# OpenMV-Main.net
KiCad netlist of a schematic drawn in Altium Designer
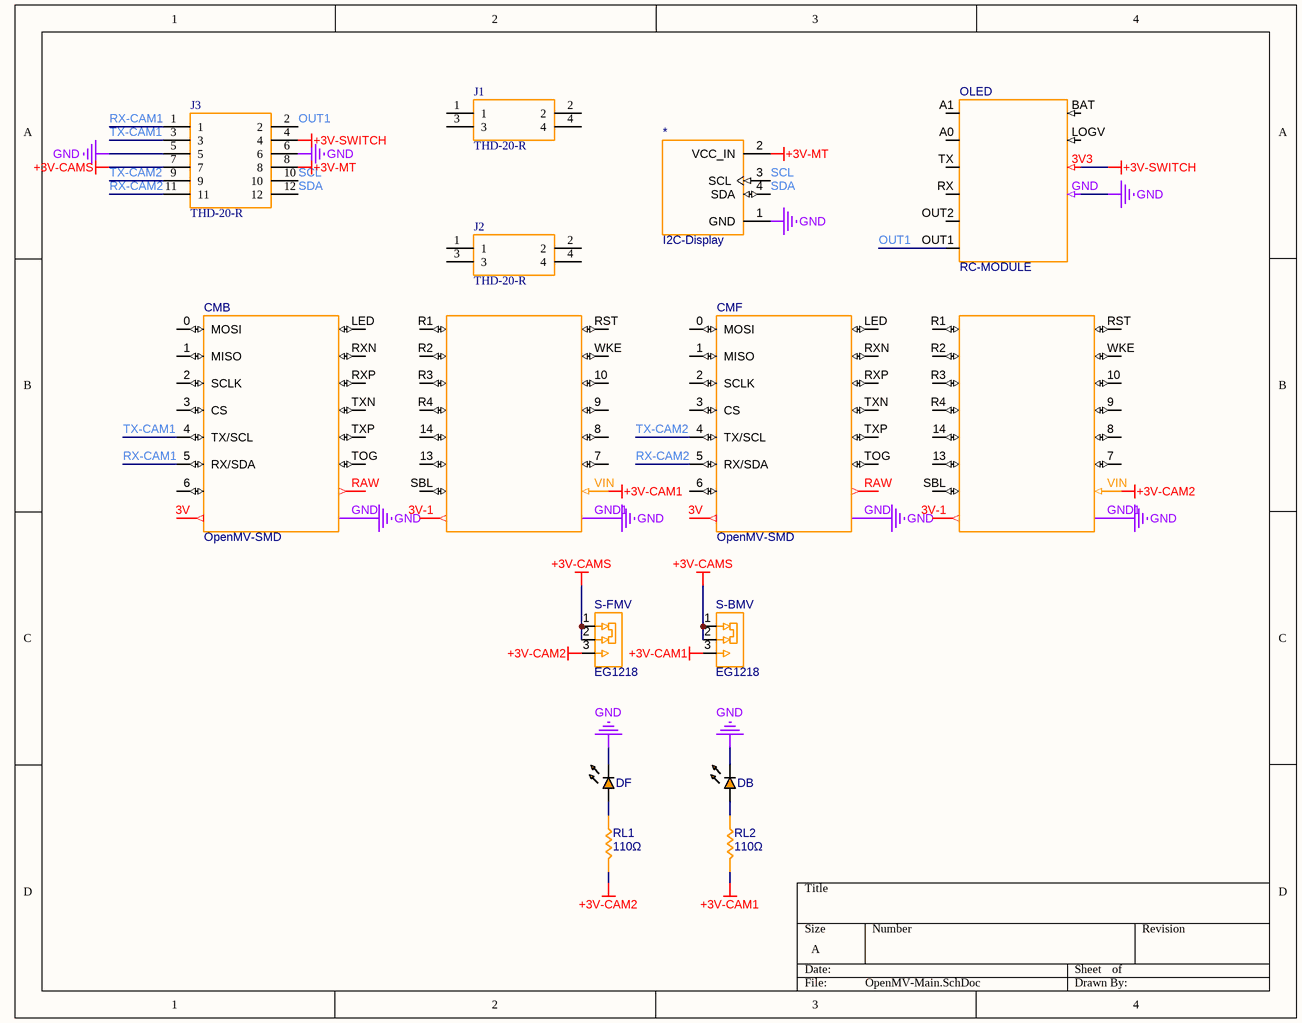
[diagram p0: OpenMV-Main.SchDoc]

(export (version "E")
  (design (tool "Eeschema 10.0.6"))
  (components
    (comp (ref "*")
      (value "I2C-Display")
      (footprint "I2C-Display")
      (libsource (lib "RC") (part "I2C-Display"))
    )
    (comp (ref "CMB")
      (value "OpenMV-SMD")
      (footprint "OpenMV-SMD")
      (libsource (lib "RC") (part "OpenMV-SMD"))
    )
    (comp (ref "CMF")
      (value "OpenMV-SMD")
      (footprint "OpenMV-SMD")
      (libsource (lib "RC") (part "OpenMV-SMD"))
    )
    (comp (ref "DB")
      (value "LED_0603")
      (footprint "LED_0603")
      (libsource (lib "GenericRC") (part "LED_0603"))
    )
    (comp (ref "DF")
      (value "LED_0603")
      (footprint "LED_0603")
      (libsource (lib "GenericRC") (part "LED_0603"))
    )
    (comp (ref "J1")
      (value "THD-20-R")
      (footprint "VALCON_THD-20-R")
      (description "THD - Valcon 2.54mm Pitch Dual Row Pin Header - Fast Stock")
      (fields (field (name "MF") "Valcon"))
      (libsource (lib "THD-20-R") (part "THD-20-R"))
    )
    (comp (ref "J2")
      (value "THD-20-R")
      (footprint "VALCON_THD-20-R")
      (description "THD - Valcon 2.54mm Pitch Dual Row Pin Header - Fast Stock")
      (fields (field (name "MF") "Valcon"))
      (libsource (lib "THD-20-R") (part "THD-20-R"))
    )
    (comp (ref "J3")
      (value "THD-20-R")
      (footprint "VALCON_THD-20-R")
      (description "THD - Valcon 2.54mm Pitch Dual Row Pin Header - Fast Stock")
      (fields (field (name "MF") "Valcon"))
      (libsource (lib "THD-12-R") (part "THD-20-R"))
    )
    (comp (ref "OLED") (value "RC-MODULE") (footprint "RC-MODULE") (libsource (lib "RC") (part "RC-MODULE")))
    (comp (ref "RL1")
      (value "110Ω")
      (footprint "RES_0603")
      (description "Resistor SMD 0603 generic")
      (libsource (lib "GenericRC") (part "RES_0603"))
    )
    (comp (ref "RL2")
      (value "110Ω")
      (footprint "RES_0603")
      (description "Resistor SMD 0603 generic")
      (libsource (lib "GenericRC") (part "RES_0603"))
    )
    (comp (ref "S-BMV")
      (value "EG1218")
      (footprint "EG1218")
      (libsource (lib "ChaBots Phoenix") (part "EG1218"))
    )
    (comp (ref "S-FMV")
      (value "EG1218")
      (footprint "EG1218")
      (libsource (lib "ChaBots Phoenix") (part "EG1218"))
    )
  )
  (nets
    (net (code "1") (name "+3V-CAM1") (class "Default")
      (node (ref "CMB") (pin "VIN") (pintype "input"))
      (node (ref "RL2") (pin "1") (pintype "passive"))
      (node (ref "S-BMV") (pin "3") (pinfunction "NO_3") (pintype "passive"))
    )
    (net (code "2") (name "+3V-CAM2") (class "Default")
      (node (ref "CMF") (pin "VIN") (pintype "input"))
      (node (ref "RL1") (pin "1") (pintype "passive"))
      (node (ref "S-FMV") (pin "3") (pinfunction "NO_3") (pintype "passive"))
    )
    (net (code "3") (name "+3V-CAMS") (class "Default")
      (node (ref "J3") (pin "7") (pinfunction "7_7") (pintype "passive"))
      (node (ref "S-BMV") (pin "1") (pinfunction "NC_1") (pintype "passive"))
      (node (ref "S-BMV") (pin "2") (pinfunction "COM_2") (pintype "passive"))
      (node (ref "S-FMV") (pin "1") (pinfunction "NC_1") (pintype "passive"))
      (node (ref "S-FMV") (pin "2") (pinfunction "COM_2") (pintype "passive"))
    )
    (net (code "4") (name "+3V-MT") (class "Default")
      (node (ref "*") (pin "2") (pinfunction "VCC_IN_2") (pintype "power_in"))
      (node (ref "J3") (pin "8") (pinfunction "8_8") (pintype "passive"))
    )
    (net (code "5") (name "+3V-SWITCH") (class "Default")
      (node (ref "J3") (pin "4") (pinfunction "4_4") (pintype "passive"))
      (node (ref "OLED") (pin "3V3") (pintype "input"))
    )
    (net (code "6") (name "/OUT1") (class "Default")
      (node (ref "J3") (pin "2") (pinfunction "2_2") (pintype "passive"))
      (node (ref "OLED") (pin "OUT1") (pintype "bidirectional"))
    )
    (net (code "7") (name "/RX-CAM1") (class "Default")
      (node (ref "CMB") (pin "5") (pinfunction "RX/SDA_5") (pintype "bidirectional"))
      (node (ref "J3") (pin "1") (pinfunction "1_1") (pintype "passive"))
    )
    (net (code "8") (name "/RX-CAM2") (class "Default")
      (node (ref "CMF") (pin "5") (pinfunction "RX/SDA_5") (pintype "bidirectional"))
      (node (ref "J3") (pin "11") (pinfunction "11_11") (pintype "passive"))
    )
    (net (code "9") (name "/SCL") (class "Default")
      (node (ref "*") (pin "3") (pinfunction "SCL_3") (pintype "input"))
      (node (ref "J3") (pin "10") (pinfunction "10_10") (pintype "passive"))
    )
    (net (code "10") (name "/SDA") (class "Default")
      (node (ref "*") (pin "4") (pinfunction "SDA_4") (pintype "bidirectional"))
      (node (ref "J3") (pin "12") (pinfunction "12_12") (pintype "passive"))
    )
    (net (code "11") (name "/TX-CAM1") (class "Default")
      (node (ref "CMB") (pin "4") (pinfunction "TX/SCL_4") (pintype "bidirectional"))
      (node (ref "J3") (pin "3") (pinfunction "3_3") (pintype "passive"))
    )
    (net (code "12") (name "/TX-CAM2") (class "Default")
      (node (ref "CMF") (pin "4") (pinfunction "TX/SCL_4") (pintype "bidirectional"))
      (node (ref "J3") (pin "9") (pinfunction "9_9") (pintype "passive"))
    )
    (net (code "13") (name "GND") (class "Default")
      (node (ref "*") (pin "1") (pinfunction "GND_1") (pintype "power_in"))
      (node (ref "CMB") (pin "GND") (pintype "passive"))
      (node (ref "CMB") (pin "GND1") (pintype "passive"))
      (node (ref "CMF") (pin "GND") (pintype "passive"))
      (node (ref "CMF") (pin "GND1") (pintype "passive"))
      (node (ref "DB") (pin "C") (pinfunction "1_C") (pintype "passive"))
      (node (ref "DF") (pin "C") (pinfunction "1_C") (pintype "passive"))
      (node (ref "J3") (pin "5") (pinfunction "5_5") (pintype "passive"))
      (node (ref "J3") (pin "6") (pinfunction "6_6") (pintype "passive"))
      (node (ref "OLED") (pin "GND") (pintype "input"))
    )
    (net (code "14") (name "Net-(DB-2)") (class "Default")
      (node (ref "DB") (pin "A") (pinfunction "2_A") (pintype "passive"))
      (node (ref "RL2") (pin "2") (pintype "passive"))
    )
    (net (code "15") (name "Net-(DF-2)") (class "Default")
      (node (ref "DF") (pin "A") (pinfunction "2_A") (pintype "passive"))
      (node (ref "RL1") (pin "2") (pintype "passive"))
    )
    (net (code "16") (name "unconnected-(CMB-CS-Pad3)") (class "Default")
      (node (ref "CMB") (pin "3") (pinfunction "CS_3") (pintype "bidirectional"))
    )
    (net (code "17") (name "unconnected-(CMB-MISO-Pad1)") (class "Default")
      (node (ref "CMB") (pin "1") (pinfunction "MISO_1") (pintype "bidirectional"))
    )
    (net (code "18") (name "unconnected-(CMB-MOSI-Pad0)") (class "Default")
      (node (ref "CMB") (pin "0") (pinfunction "MOSI_0") (pintype "bidirectional"))
    )
    (net (code "19") (name "unconnected-(CMB-Pad3V)") (class "Default")
      (node (ref "CMB") (pin "3V") (pintype "output"))
    )
    (net (code "20") (name "unconnected-(CMB-Pad3V-1)") (class "Default")
      (node (ref "CMB") (pin "3V-1") (pintype "output"))
    )
    (net (code "21") (name "unconnected-(CMB-Pad6)") (class "Default")
      (node (ref "CMB") (pin "6") (pintype "bidirectional"))
    )
    (net (code "22") (name "unconnected-(CMB-Pad7)") (class "Default")
      (node (ref "CMB") (pin "7") (pintype "bidirectional"))
    )
    (net (code "23") (name "unconnected-(CMB-Pad8)") (class "Default")
      (node (ref "CMB") (pin "8") (pintype "bidirectional"))
    )
    (net (code "24") (name "unconnected-(CMB-Pad9)") (class "Default")
      (node (ref "CMB") (pin "9") (pintype "bidirectional"))
    )
    (net (code "25") (name "unconnected-(CMB-Pad10)") (class "Default")
      (node (ref "CMB") (pin "10") (pintype "bidirectional"))
    )
    (net (code "26") (name "unconnected-(CMB-Pad13)") (class "Default")
      (node (ref "CMB") (pin "13") (pintype "bidirectional"))
    )
    (net (code "27") (name "unconnected-(CMB-Pad14)") (class "Default")
      (node (ref "CMB") (pin "14") (pintype "bidirectional"))
    )
    (net (code "28") (name "unconnected-(CMB-PadLED)") (class "Default")
      (node (ref "CMB") (pin "LED") (pintype "bidirectional"))
    )
    (net (code "29") (name "unconnected-(CMB-PadR1)") (class "Default")
      (node (ref "CMB") (pin "R1") (pintype "bidirectional"))
    )
    (net (code "30") (name "unconnected-(CMB-PadR2)") (class "Default")
      (node (ref "CMB") (pin "R2") (pintype "bidirectional"))
    )
    (net (code "31") (name "unconnected-(CMB-PadR3)") (class "Default")
      (node (ref "CMB") (pin "R3") (pintype "bidirectional"))
    )
    (net (code "32") (name "unconnected-(CMB-PadR4)") (class "Default")
      (node (ref "CMB") (pin "R4") (pintype "bidirectional"))
    )
    (net (code "33") (name "unconnected-(CMB-PadRAW)") (class "Default")
      (node (ref "CMB") (pin "RAW") (pintype "output"))
    )
    (net (code "34") (name "unconnected-(CMB-PadRST)") (class "Default")
      (node (ref "CMB") (pin "RST") (pintype "bidirectional"))
    )
    (net (code "35") (name "unconnected-(CMB-PadRXN)") (class "Default")
      (node (ref "CMB") (pin "RXN") (pintype "bidirectional"))
    )
    (net (code "36") (name "unconnected-(CMB-PadRXP)") (class "Default")
      (node (ref "CMB") (pin "RXP") (pintype "bidirectional"))
    )
    (net (code "37") (name "unconnected-(CMB-PadSBL)") (class "Default")
      (node (ref "CMB") (pin "SBL") (pintype "bidirectional"))
    )
    (net (code "38") (name "unconnected-(CMB-PadTOG)") (class "Default")
      (node (ref "CMB") (pin "TOG") (pintype "bidirectional"))
    )
    (net (code "39") (name "unconnected-(CMB-PadTXN)") (class "Default")
      (node (ref "CMB") (pin "TXN") (pintype "bidirectional"))
    )
    (net (code "40") (name "unconnected-(CMB-PadTXP)") (class "Default")
      (node (ref "CMB") (pin "TXP") (pintype "bidirectional"))
    )
    (net (code "41") (name "unconnected-(CMB-PadWKE)") (class "Default")
      (node (ref "CMB") (pin "WKE") (pintype "bidirectional"))
    )
    (net (code "42") (name "unconnected-(CMB-SCLK-Pad2)") (class "Default")
      (node (ref "CMB") (pin "2") (pinfunction "SCLK_2") (pintype "bidirectional"))
    )
    (net (code "43") (name "unconnected-(CMF-CS-Pad3)") (class "Default")
      (node (ref "CMF") (pin "3") (pinfunction "CS_3") (pintype "bidirectional"))
    )
    (net (code "44") (name "unconnected-(CMF-MISO-Pad1)") (class "Default")
      (node (ref "CMF") (pin "1") (pinfunction "MISO_1") (pintype "bidirectional"))
    )
    (net (code "45") (name "unconnected-(CMF-MOSI-Pad0)") (class "Default")
      (node (ref "CMF") (pin "0") (pinfunction "MOSI_0") (pintype "bidirectional"))
    )
    (net (code "46") (name "unconnected-(CMF-Pad3V)") (class "Default")
      (node (ref "CMF") (pin "3V") (pintype "output"))
    )
    (net (code "47") (name "unconnected-(CMF-Pad3V-1)") (class "Default")
      (node (ref "CMF") (pin "3V-1") (pintype "output"))
    )
    (net (code "48") (name "unconnected-(CMF-Pad6)") (class "Default")
      (node (ref "CMF") (pin "6") (pintype "bidirectional"))
    )
    (net (code "49") (name "unconnected-(CMF-Pad7)") (class "Default")
      (node (ref "CMF") (pin "7") (pintype "bidirectional"))
    )
    (net (code "50") (name "unconnected-(CMF-Pad8)") (class "Default")
      (node (ref "CMF") (pin "8") (pintype "bidirectional"))
    )
    (net (code "51") (name "unconnected-(CMF-Pad9)") (class "Default")
      (node (ref "CMF") (pin "9") (pintype "bidirectional"))
    )
    (net (code "52") (name "unconnected-(CMF-Pad10)") (class "Default")
      (node (ref "CMF") (pin "10") (pintype "bidirectional"))
    )
    (net (code "53") (name "unconnected-(CMF-Pad13)") (class "Default")
      (node (ref "CMF") (pin "13") (pintype "bidirectional"))
    )
    (net (code "54") (name "unconnected-(CMF-Pad14)") (class "Default")
      (node (ref "CMF") (pin "14") (pintype "bidirectional"))
    )
    (net (code "55") (name "unconnected-(CMF-PadLED)") (class "Default")
      (node (ref "CMF") (pin "LED") (pintype "bidirectional"))
    )
    (net (code "56") (name "unconnected-(CMF-PadR1)") (class "Default")
      (node (ref "CMF") (pin "R1") (pintype "bidirectional"))
    )
    (net (code "57") (name "unconnected-(CMF-PadR2)") (class "Default")
      (node (ref "CMF") (pin "R2") (pintype "bidirectional"))
    )
    (net (code "58") (name "unconnected-(CMF-PadR3)") (class "Default")
      (node (ref "CMF") (pin "R3") (pintype "bidirectional"))
    )
    (net (code "59") (name "unconnected-(CMF-PadR4)") (class "Default")
      (node (ref "CMF") (pin "R4") (pintype "bidirectional"))
    )
    (net (code "60") (name "unconnected-(CMF-PadRAW)") (class "Default")
      (node (ref "CMF") (pin "RAW") (pintype "output"))
    )
    (net (code "61") (name "unconnected-(CMF-PadRST)") (class "Default")
      (node (ref "CMF") (pin "RST") (pintype "bidirectional"))
    )
    (net (code "62") (name "unconnected-(CMF-PadRXN)") (class "Default")
      (node (ref "CMF") (pin "RXN") (pintype "bidirectional"))
    )
    (net (code "63") (name "unconnected-(CMF-PadRXP)") (class "Default")
      (node (ref "CMF") (pin "RXP") (pintype "bidirectional"))
    )
    (net (code "64") (name "unconnected-(CMF-PadSBL)") (class "Default")
      (node (ref "CMF") (pin "SBL") (pintype "bidirectional"))
    )
    (net (code "65") (name "unconnected-(CMF-PadTOG)") (class "Default")
      (node (ref "CMF") (pin "TOG") (pintype "bidirectional"))
    )
    (net (code "66") (name "unconnected-(CMF-PadTXN)") (class "Default")
      (node (ref "CMF") (pin "TXN") (pintype "bidirectional"))
    )
    (net (code "67") (name "unconnected-(CMF-PadTXP)") (class "Default")
      (node (ref "CMF") (pin "TXP") (pintype "bidirectional"))
    )
    (net (code "68") (name "unconnected-(CMF-PadWKE)") (class "Default")
      (node (ref "CMF") (pin "WKE") (pintype "bidirectional"))
    )
    (net (code "69") (name "unconnected-(CMF-SCLK-Pad2)") (class "Default")
      (node (ref "CMF") (pin "2") (pinfunction "SCLK_2") (pintype "bidirectional"))
    )
    (net (code "70") (name "unconnected-(J1-Pad1)") (class "Default")
      (node (ref "J1") (pin "1") (pinfunction "1_1") (pintype "passive"))
    )
    (net (code "71") (name "unconnected-(J1-Pad2)") (class "Default")
      (node (ref "J1") (pin "2") (pinfunction "2_2") (pintype "passive"))
    )
    (net (code "72") (name "unconnected-(J1-Pad3)") (class "Default")
      (node (ref "J1") (pin "3") (pinfunction "3_3") (pintype "passive"))
    )
    (net (code "73") (name "unconnected-(J1-Pad4)") (class "Default")
      (node (ref "J1") (pin "4") (pinfunction "4_4") (pintype "passive"))
    )
    (net (code "74") (name "unconnected-(J2-Pad1)") (class "Default")
      (node (ref "J2") (pin "1") (pinfunction "1_1") (pintype "passive"))
    )
    (net (code "75") (name "unconnected-(J2-Pad2)") (class "Default")
      (node (ref "J2") (pin "2") (pinfunction "2_2") (pintype "passive"))
    )
    (net (code "76") (name "unconnected-(J2-Pad3)") (class "Default")
      (node (ref "J2") (pin "3") (pinfunction "3_3") (pintype "passive"))
    )
    (net (code "77") (name "unconnected-(J2-Pad4)") (class "Default")
      (node (ref "J2") (pin "4") (pinfunction "4_4") (pintype "passive"))
    )
    (net (code "78") (name "unconnected-(OLED-PadA0)") (class "Default")
      (node (ref "OLED") (pin "A0") (pintype "bidirectional"))
    )
    (net (code "79") (name "unconnected-(OLED-PadA1)") (class "Default")
      (node (ref "OLED") (pin "A1") (pintype "bidirectional"))
    )
    (net (code "80") (name "unconnected-(OLED-PadBAT)") (class "Default")
      (node (ref "OLED") (pin "BAT") (pintype "input"))
    )
    (net (code "81") (name "unconnected-(OLED-PadLOGV)") (class "Default")
      (node (ref "OLED") (pin "LOGV") (pintype "input"))
    )
    (net (code "82") (name "unconnected-(OLED-PadOUT2)") (class "Default")
      (node (ref "OLED") (pin "OUT2") (pintype "bidirectional"))
    )
    (net (code "83") (name "unconnected-(OLED-PadRX)") (class "Default")
      (node (ref "OLED") (pin "RX") (pintype "bidirectional"))
    )
    (net (code "84") (name "unconnected-(OLED-PadTX)") (class "Default")
      (node (ref "OLED") (pin "TX") (pintype "bidirectional"))
    )
  )
)
